# M627C.net
KiCad netlist of a schematic drawn in EAGLE
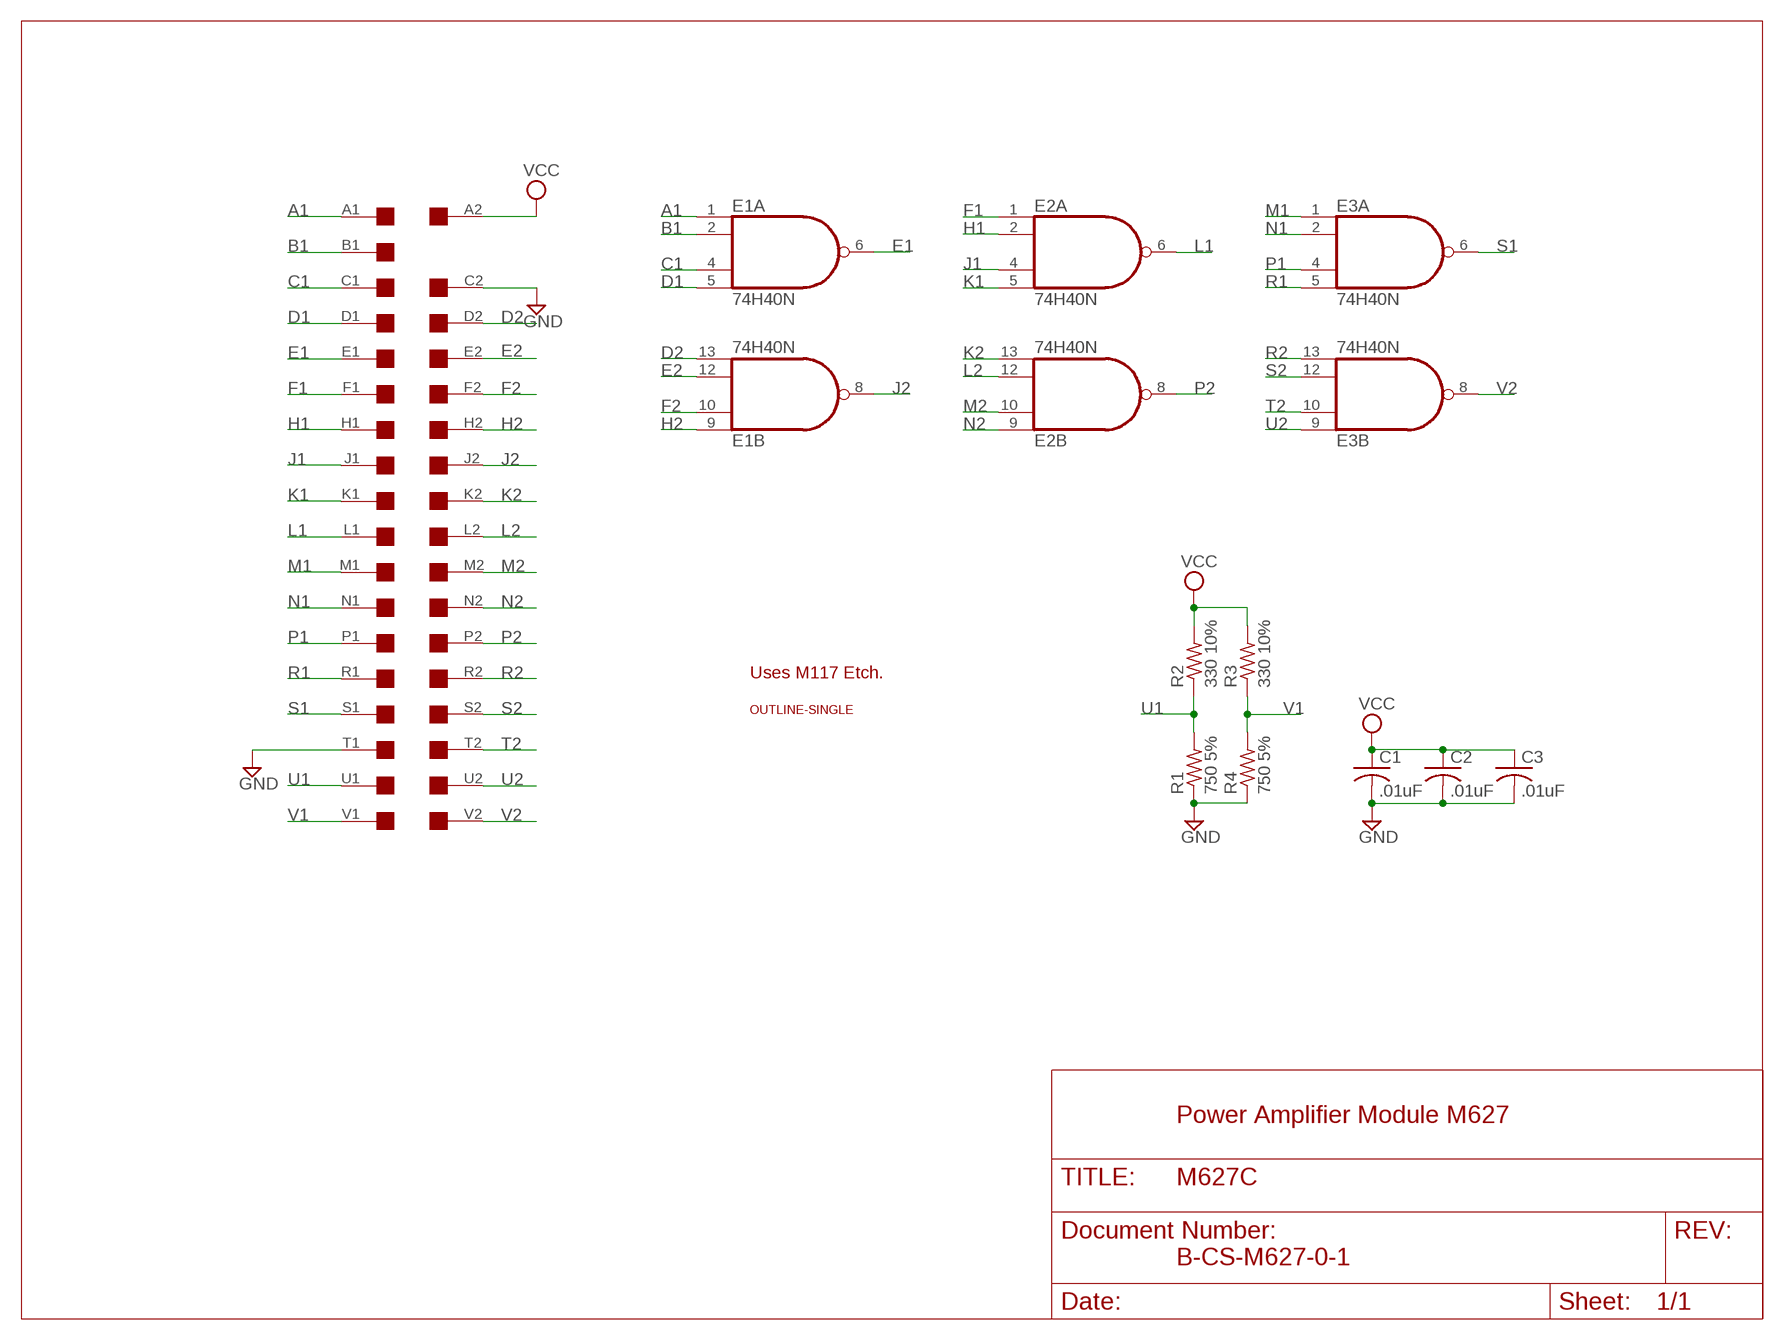
[diagram p0: schematic, sheet 1]

(export (version "E")
  (design (tool "Eeschema 10.0.6"))
  (components
    (comp (ref "C1")
      (value ".01uF")
      (footprint "eagle-import:C050-025X075")
      (libsource (lib "eagle-import") (part "C-US050-025X075"))
    )
    (comp (ref "C2")
      (value ".01uF")
      (footprint "eagle-import:C050-025X075")
      (libsource (lib "eagle-import") (part "C-US050-025X075"))
    )
    (comp (ref "C3")
      (value ".01uF")
      (footprint "eagle-import:C050-025X075")
      (libsource (lib "eagle-import") (part "C-US050-025X075"))
    )
    (comp (ref "E1")
      (value "74H40N")
      (footprint "eagle-import:DIL14")
      (libsource (lib "eagle-import") (part "7420NS"))
    )
    (comp (ref "E2")
      (value "74H40N")
      (footprint "eagle-import:DIL14")
      (libsource (lib "eagle-import") (part "7420NS"))
    )
    (comp (ref "E3")
      (value "74H40N")
      (footprint "eagle-import:DIL14")
      (libsource (lib "eagle-import") (part "7420NS"))
    )
    (comp (ref "R1")
      (value "750 5%")
      (footprint "eagle-import:0207_10")
      (libsource (lib "eagle-import") (part "R-US_0207/10"))
    )
    (comp (ref "R2")
      (value "330 10%")
      (footprint "eagle-import:0207_10")
      (libsource (lib "eagle-import") (part "R-US_0207/10"))
    )
    (comp (ref "R3")
      (value "330 10%")
      (footprint "eagle-import:0207_10")
      (libsource (lib "eagle-import") (part "R-US_0207/10"))
    )
    (comp (ref "R4")
      (value "750 5%")
      (footprint "eagle-import:0207_10")
      (libsource (lib "eagle-import") (part "R-US_0207/10"))
    )
    (comp (ref "U$1")
      (value "SINGLE")
      (footprint "eagle-import:EDGE-CON2")
      (libsource (lib "eagle-import") (part "SINGLE"))
    )
    (comp (ref "U$4")
      (value "OUTLINE-SINGLE")
      (footprint "eagle-import:SINGLE")
      (libsource (lib "eagle-import") (part "OUTLINE-SINGLE"))
    )
  )
  (nets
    (net (code "1") (name "/A1") (class "Default")
      (node (ref "E1") (pin "1") (pinfunction "I0_1") (pintype "input"))
      (node (ref "U$1") (pin "A1") (pinfunction "1_A1") (pintype "bidirectional"))
    )
    (net (code "2") (name "/B1") (class "Default")
      (node (ref "E1") (pin "2") (pinfunction "I1_2") (pintype "input"))
      (node (ref "U$1") (pin "B1") (pinfunction "1_B1") (pintype "bidirectional"))
    )
    (net (code "3") (name "/C1") (class "Default")
      (node (ref "E1") (pin "4") (pinfunction "I2_4") (pintype "input"))
      (node (ref "U$1") (pin "C1") (pinfunction "1_C1") (pintype "bidirectional"))
    )
    (net (code "4") (name "/D1") (class "Default")
      (node (ref "E1") (pin "5") (pinfunction "I3_5") (pintype "input"))
      (node (ref "U$1") (pin "D1") (pinfunction "1_D1") (pintype "bidirectional"))
    )
    (net (code "5") (name "/D2") (class "Default")
      (node (ref "E1") (pin "13") (pinfunction "I3_13") (pintype "input"))
      (node (ref "U$1") (pin "D2") (pinfunction "1_D2") (pintype "bidirectional"))
    )
    (net (code "6") (name "/E1") (class "Default")
      (node (ref "E1") (pin "6") (pinfunction "O_6") (pintype "output"))
      (node (ref "U$1") (pin "E1") (pinfunction "1_E1") (pintype "bidirectional"))
    )
    (net (code "7") (name "/E2") (class "Default")
      (node (ref "E1") (pin "12") (pinfunction "I2_12") (pintype "input"))
      (node (ref "U$1") (pin "E2") (pinfunction "1_E2") (pintype "bidirectional"))
    )
    (net (code "8") (name "/F1") (class "Default")
      (node (ref "E2") (pin "1") (pinfunction "I0_1") (pintype "input"))
      (node (ref "U$1") (pin "F1") (pinfunction "1_F1") (pintype "bidirectional"))
    )
    (net (code "9") (name "/F2") (class "Default")
      (node (ref "E1") (pin "10") (pinfunction "I1_10") (pintype "input"))
      (node (ref "U$1") (pin "F2") (pinfunction "1_F2") (pintype "bidirectional"))
    )
    (net (code "10") (name "/H1") (class "Default")
      (node (ref "E2") (pin "2") (pinfunction "I1_2") (pintype "input"))
      (node (ref "U$1") (pin "H1") (pinfunction "1_H1") (pintype "bidirectional"))
    )
    (net (code "11") (name "/H2") (class "Default")
      (node (ref "E1") (pin "9") (pinfunction "I0_9") (pintype "input"))
      (node (ref "U$1") (pin "H2") (pinfunction "1_H2") (pintype "bidirectional"))
    )
    (net (code "12") (name "/J1") (class "Default")
      (node (ref "E2") (pin "4") (pinfunction "I2_4") (pintype "input"))
      (node (ref "U$1") (pin "J1") (pinfunction "1_J1") (pintype "bidirectional"))
    )
    (net (code "13") (name "/J2") (class "Default")
      (node (ref "E1") (pin "8") (pinfunction "O_8") (pintype "output"))
      (node (ref "U$1") (pin "J2") (pinfunction "1_J2") (pintype "bidirectional"))
    )
    (net (code "14") (name "/K1") (class "Default")
      (node (ref "E2") (pin "5") (pinfunction "I3_5") (pintype "input"))
      (node (ref "U$1") (pin "K1") (pinfunction "1_K1") (pintype "bidirectional"))
    )
    (net (code "15") (name "/K2") (class "Default")
      (node (ref "E2") (pin "13") (pinfunction "I3_13") (pintype "input"))
      (node (ref "U$1") (pin "K2") (pinfunction "1_K2") (pintype "bidirectional"))
    )
    (net (code "16") (name "/L1") (class "Default")
      (node (ref "E2") (pin "6") (pinfunction "O_6") (pintype "output"))
      (node (ref "U$1") (pin "L1") (pinfunction "1_L1") (pintype "bidirectional"))
    )
    (net (code "17") (name "/L2") (class "Default")
      (node (ref "E2") (pin "12") (pinfunction "I2_12") (pintype "input"))
      (node (ref "U$1") (pin "L2") (pinfunction "1_L2") (pintype "bidirectional"))
    )
    (net (code "18") (name "/M1") (class "Default")
      (node (ref "E3") (pin "1") (pinfunction "I0_1") (pintype "input"))
      (node (ref "U$1") (pin "M1") (pinfunction "1_M1") (pintype "bidirectional"))
    )
    (net (code "19") (name "/M2") (class "Default")
      (node (ref "E2") (pin "10") (pinfunction "I1_10") (pintype "input"))
      (node (ref "U$1") (pin "M2") (pinfunction "1_M2") (pintype "bidirectional"))
    )
    (net (code "20") (name "/N1") (class "Default")
      (node (ref "E3") (pin "2") (pinfunction "I1_2") (pintype "input"))
      (node (ref "U$1") (pin "N1") (pinfunction "1_N1") (pintype "bidirectional"))
    )
    (net (code "21") (name "/N2") (class "Default")
      (node (ref "E2") (pin "9") (pinfunction "I0_9") (pintype "input"))
      (node (ref "U$1") (pin "N2") (pinfunction "1_N2") (pintype "bidirectional"))
    )
    (net (code "22") (name "/P1") (class "Default")
      (node (ref "E3") (pin "4") (pinfunction "I2_4") (pintype "input"))
      (node (ref "U$1") (pin "P1") (pinfunction "1_P1") (pintype "bidirectional"))
    )
    (net (code "23") (name "/P2") (class "Default")
      (node (ref "E2") (pin "8") (pinfunction "O_8") (pintype "output"))
      (node (ref "U$1") (pin "P2") (pinfunction "1_P2") (pintype "bidirectional"))
    )
    (net (code "24") (name "/R1") (class "Default")
      (node (ref "E3") (pin "5") (pinfunction "I3_5") (pintype "input"))
      (node (ref "U$1") (pin "R1") (pinfunction "1_R1") (pintype "bidirectional"))
    )
    (net (code "25") (name "/R2") (class "Default")
      (node (ref "E3") (pin "13") (pinfunction "I3_13") (pintype "input"))
      (node (ref "U$1") (pin "R2") (pinfunction "1_R2") (pintype "bidirectional"))
    )
    (net (code "26") (name "/S1") (class "Default")
      (node (ref "E3") (pin "6") (pinfunction "O_6") (pintype "output"))
      (node (ref "U$1") (pin "S1") (pinfunction "1_S1") (pintype "bidirectional"))
    )
    (net (code "27") (name "/S2") (class "Default")
      (node (ref "E3") (pin "12") (pinfunction "I2_12") (pintype "input"))
      (node (ref "U$1") (pin "S2") (pinfunction "1_S2") (pintype "bidirectional"))
    )
    (net (code "28") (name "/T2") (class "Default")
      (node (ref "E3") (pin "10") (pinfunction "I1_10") (pintype "input"))
      (node (ref "U$1") (pin "T2") (pinfunction "1_T2") (pintype "bidirectional"))
    )
    (net (code "29") (name "/U1") (class "Default")
      (node (ref "R1") (pin "2") (pinfunction "2_2") (pintype "passive"))
      (node (ref "R2") (pin "1") (pinfunction "1_1") (pintype "passive"))
      (node (ref "U$1") (pin "U1") (pinfunction "1_U1") (pintype "bidirectional"))
    )
    (net (code "30") (name "/U2") (class "Default")
      (node (ref "E3") (pin "9") (pinfunction "I0_9") (pintype "input"))
      (node (ref "U$1") (pin "U2") (pinfunction "1_U2") (pintype "bidirectional"))
    )
    (net (code "31") (name "/V1") (class "Default")
      (node (ref "R3") (pin "1") (pinfunction "1_1") (pintype "passive"))
      (node (ref "R4") (pin "2") (pinfunction "2_2") (pintype "passive"))
      (node (ref "U$1") (pin "V1") (pinfunction "1_V1") (pintype "bidirectional"))
    )
    (net (code "32") (name "/V2") (class "Default")
      (node (ref "E3") (pin "8") (pinfunction "O_8") (pintype "output"))
      (node (ref "U$1") (pin "V2") (pinfunction "1_V2") (pintype "bidirectional"))
    )
    (net (code "33") (name "GND") (class "Default")
      (node (ref "C1") (pin "2") (pinfunction "2_2") (pintype "passive"))
      (node (ref "C2") (pin "2") (pinfunction "2_2") (pintype "passive"))
      (node (ref "C3") (pin "2") (pinfunction "2_2") (pintype "passive"))
      (node (ref "R1") (pin "1") (pinfunction "1_1") (pintype "passive"))
      (node (ref "R4") (pin "1") (pinfunction "1_1") (pintype "passive"))
      (node (ref "U$1") (pin "C2") (pinfunction "1_C2") (pintype "bidirectional"))
      (node (ref "U$1") (pin "T1") (pinfunction "1_T1") (pintype "bidirectional"))
    )
    (net (code "34") (name "VCC") (class "Default")
      (node (ref "C1") (pin "1") (pinfunction "1_1") (pintype "passive"))
      (node (ref "C2") (pin "1") (pinfunction "1_1") (pintype "passive"))
      (node (ref "C3") (pin "1") (pinfunction "1_1") (pintype "passive"))
      (node (ref "R2") (pin "2") (pinfunction "2_2") (pintype "passive"))
      (node (ref "R3") (pin "2") (pinfunction "2_2") (pintype "passive"))
      (node (ref "U$1") (pin "A2") (pinfunction "1_A2") (pintype "bidirectional"))
    )
  )
)
